# Metro_Mini_328_V2_-_STEMMA_QT.net
KiCad netlist of a schematic drawn in EAGLE
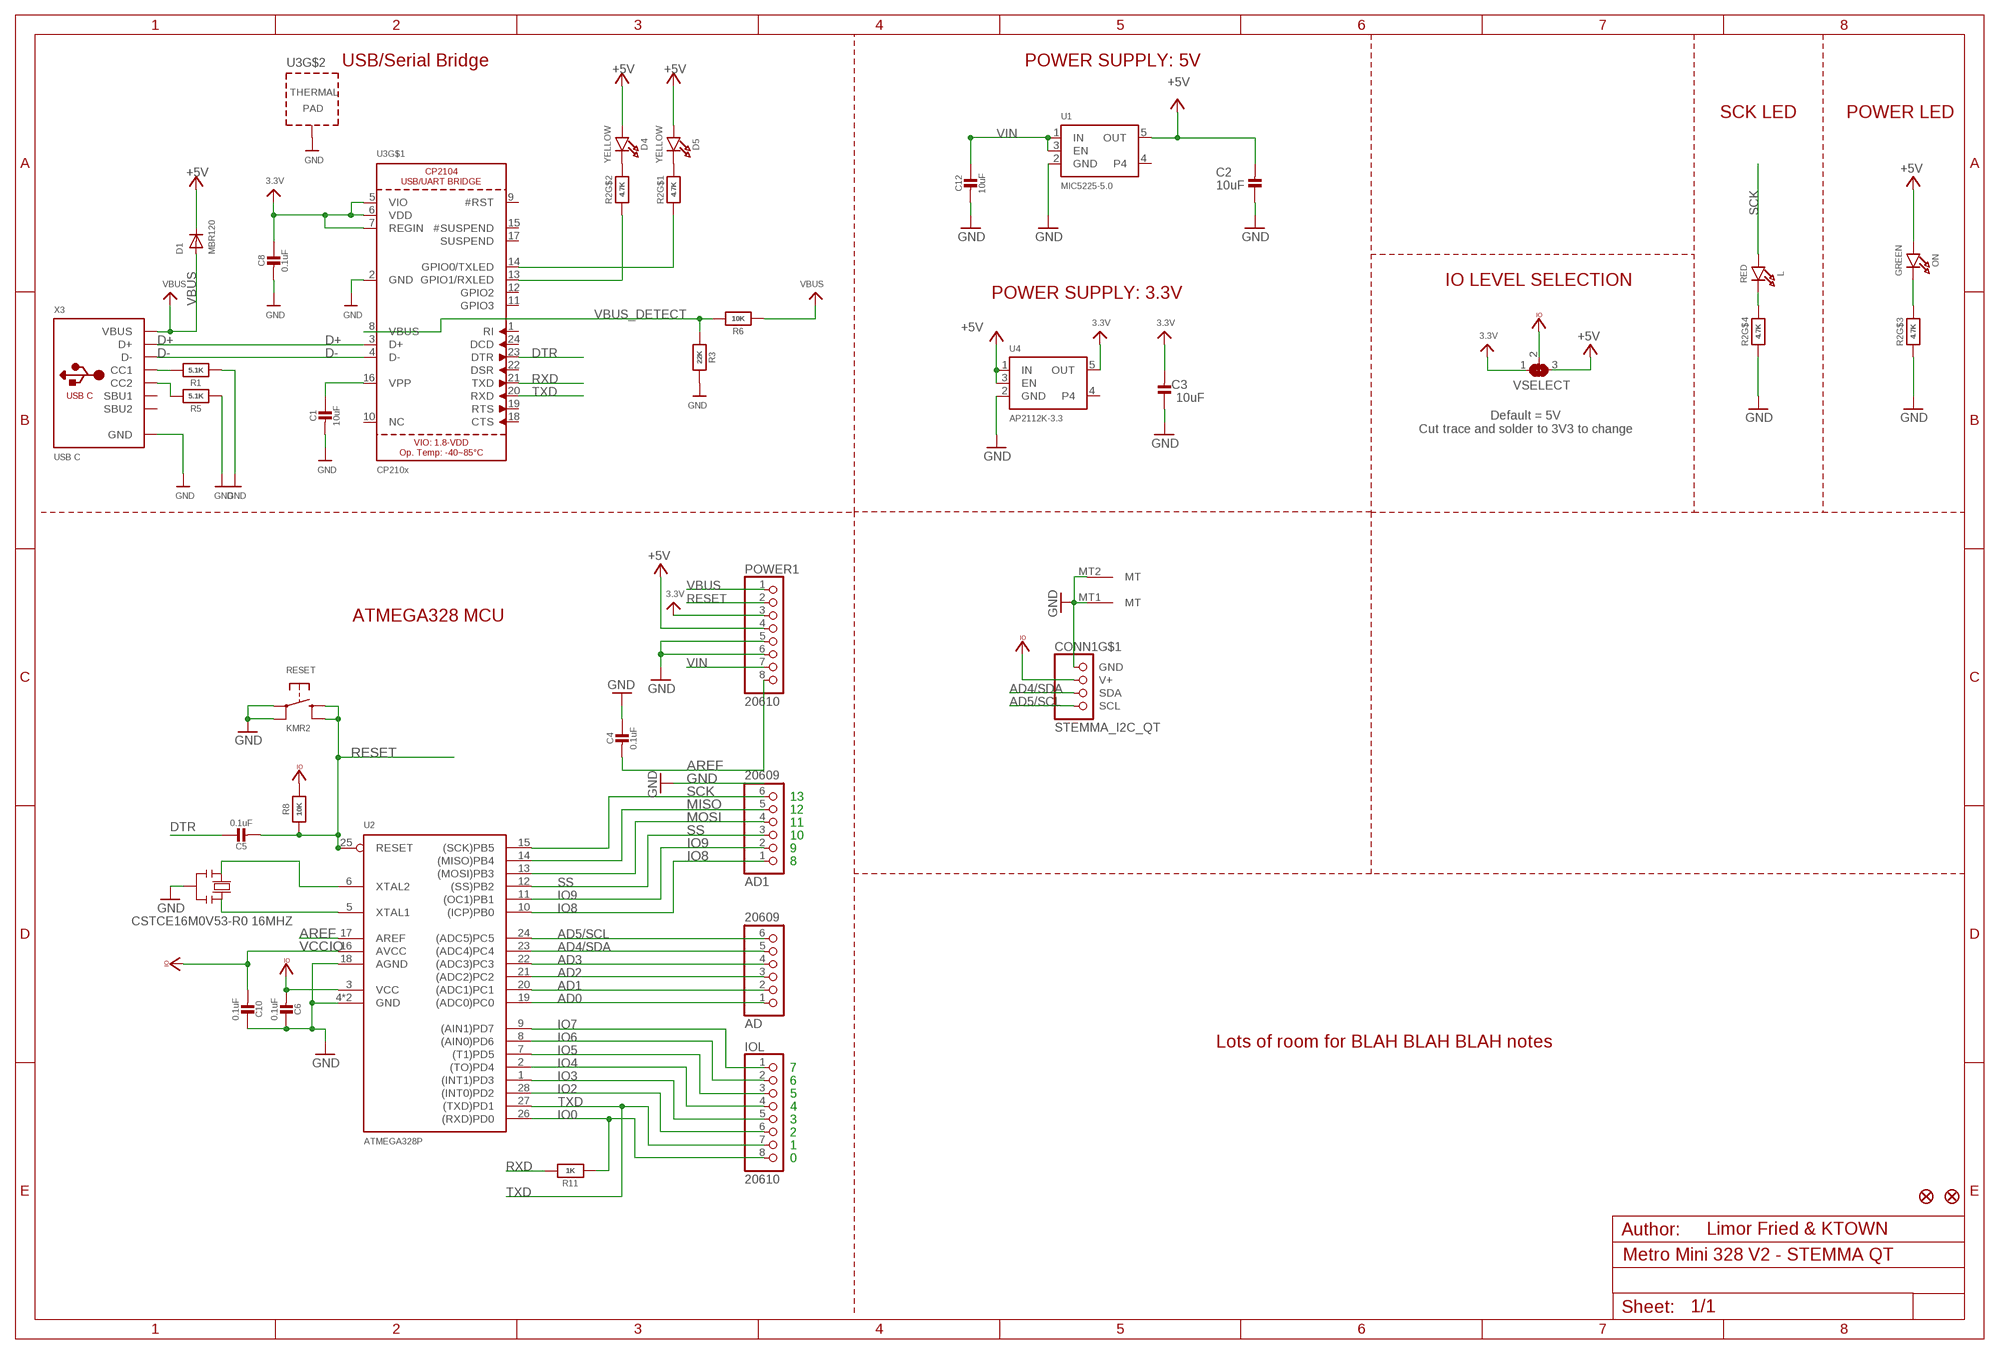
[diagram p0: schematic, sheet 1]

(export (version "E")
  (design (tool "Eeschema 10.0.6"))
  (components
    (comp (ref "AD")
      (value "20609")
      (footprint "eagle-import:1X06_ROUND")
      (libsource (lib "eagle-import") (part "HEADER-1X6ROUND"))
    )
    (comp (ref "AD1")
      (value "20609")
      (footprint "eagle-import:1X06_ROUND")
      (libsource (lib "eagle-import") (part "HEADER-1X6ROUND"))
    )
    (comp (ref "C1")
      (value "10uF")
      (footprint "eagle-import:0805-NO")
      (libsource (lib "eagle-import") (part "CAP_CERAMIC0805-NOOUTLINE"))
    )
    (comp (ref "C2")
      (value "10uF")
      (footprint "eagle-import:0805-NO")
      (libsource (lib "eagle-import") (part "CAP_CERAMIC0805-NOOUTLINE"))
    )
    (comp (ref "C3")
      (value "10uF")
      (footprint "eagle-import:0805-NO")
      (libsource (lib "eagle-import") (part "CAP_CERAMIC0805-NOOUTLINE"))
    )
    (comp (ref "C4")
      (value "0.1uF")
      (footprint "eagle-import:0603-NO")
      (libsource (lib "eagle-import") (part "CAP_CERAMIC0603_NO"))
    )
    (comp (ref "C5")
      (value "0.1uF")
      (footprint "eagle-import:0603-NO")
      (libsource (lib "eagle-import") (part "CAP_CERAMIC0603_NO"))
    )
    (comp (ref "C6")
      (value "0.1uF")
      (footprint "eagle-import:0603-NO")
      (libsource (lib "eagle-import") (part "CAP_CERAMIC0603_NO"))
    )
    (comp (ref "C8")
      (value "0.1uF")
      (footprint "eagle-import:0603-NO")
      (libsource (lib "eagle-import") (part "CAP_CERAMIC0603_NO"))
    )
    (comp (ref "C10")
      (value "0.1uF")
      (footprint "eagle-import:0603-NO")
      (libsource (lib "eagle-import") (part "CAP_CERAMIC0603_NO"))
    )
    (comp (ref "C12")
      (value "10uF")
      (footprint "eagle-import:0805-NO")
      (libsource (lib "eagle-import") (part "CAP_CERAMIC0805-NOOUTLINE"))
    )
    (comp (ref "CONN1")
      (value "STEMMA_I2C_QT")
      (footprint "eagle-import:JST_SH4")
      (libsource (lib "eagle-import") (part "STEMMA_I2C_QT"))
    )
    (comp (ref "D1")
      (value "MBR120")
      (footprint "eagle-import:SOD-123FL")
      (libsource (lib "eagle-import") (part "DIODE_MINISOD123"))
    )
    (comp (ref "D4")
      (value "YELLOW")
      (footprint "eagle-import:CHIPLED_0603_NOOUTLINE")
      (libsource (lib "eagle-import") (part "LED0603_NOOUTLINE"))
    )
    (comp (ref "D5")
      (value "YELLOW")
      (footprint "eagle-import:CHIPLED_0603_NOOUTLINE")
      (libsource (lib "eagle-import") (part "LED0603_NOOUTLINE"))
    )
    (comp (ref "FD1")
      (value "FIDUCIAL_1MM")
      (footprint "eagle-import:FIDUCIAL_1MM")
      (libsource (lib "eagle-import") (part "FIDUCIAL_1MM"))
    )
    (comp (ref "FD2")
      (value "FIDUCIAL_1MM")
      (footprint "eagle-import:FIDUCIAL_1MM")
      (libsource (lib "eagle-import") (part "FIDUCIAL_1MM"))
    )
    (comp (ref "IOL")
      (value "20610")
      (footprint "eagle-import:1X08_ROUND")
      (libsource (lib "eagle-import") (part "HEADER-1X8ROUND"))
    )
    (comp (ref "L")
      (value "RED")
      (footprint "eagle-import:CHIPLED_0603_NOOUTLINE")
      (libsource (lib "eagle-import") (part "LED0603_NOOUTLINE"))
    )
    (comp (ref "ON")
      (value "GREEN")
      (footprint "eagle-import:CHIPLED_0603_NOOUTLINE")
      (libsource (lib "eagle-import") (part "LED0603_NOOUTLINE"))
    )
    (comp (ref "POWER1")
      (value "20610")
      (footprint "eagle-import:1X08_ROUND_70")
      (libsource (lib "eagle-import") (part "HEADER-1X870MIL"))
    )
    (comp (ref "R1")
      (value "5.1K")
      (footprint "eagle-import:0603-NO")
      (libsource (lib "eagle-import") (part "RESISTOR_0603_NOOUT"))
    )
    (comp (ref "R2")
      (value "4.7K")
      (footprint "eagle-import:RESPACK_4X0603")
      (libsource (lib "eagle-import") (part "RESISTOR_4PACK"))
    )
    (comp (ref "R3")
      (value "22K")
      (footprint "eagle-import:0603-NO")
      (libsource (lib "eagle-import") (part "RESISTOR_0603_NOOUT"))
    )
    (comp (ref "R5")
      (value "5.1K")
      (footprint "eagle-import:0603-NO")
      (libsource (lib "eagle-import") (part "RESISTOR_0603_NOOUT"))
    )
    (comp (ref "R6")
      (value "10K")
      (footprint "eagle-import:0603-NO")
      (libsource (lib "eagle-import") (part "RESISTOR_0603_NOOUT"))
    )
    (comp (ref "R8")
      (value "10K")
      (footprint "eagle-import:0603-NO")
      (libsource (lib "eagle-import") (part "RESISTOR_0603_NOOUT"))
    )
    (comp (ref "R11")
      (value "1K")
      (footprint "eagle-import:0603-NO")
      (libsource (lib "eagle-import") (part "RESISTOR_0603_NOOUT"))
    )
    (comp (ref "RESET")
      (value "KMR2")
      (footprint "eagle-import:BTN_KMR2_4.6X2.8")
      (libsource (lib "eagle-import") (part "SWITCH_TACT_SMT4.6X2.8"))
    )
    (comp (ref "U1")
      (value "MIC5225-5.0")
      (footprint "eagle-import:SOT23-5")
      (libsource (lib "eagle-import") (part "VREG_SOT23-5"))
    )
    (comp (ref "U2")
      (value "ATMEGA328P")
      (footprint "eagle-import:QFN28_4MM_.45MM")
      (libsource (lib "eagle-import") (part "ATMEGA328P-MM"))
    )
    (comp (ref "U3")
      (value "CP210x")
      (footprint "eagle-import:QFN24_4MM_SMSC")
      (libsource (lib "eagle-import") (part "CP2104"))
    )
    (comp (ref "U4")
      (value "AP2112K-3.3")
      (footprint "eagle-import:SOT23-5")
      (libsource (lib "eagle-import") (part "VREG_SOT23-5"))
    )
    (comp (ref "VSELECT")
      (value "SOLDERJUMPER_2WAY")
      (footprint "eagle-import:SOLDERJUMPER_2WAY_OPEN_NOPASTE")
      (libsource (lib "eagle-import") (part "SOLDERJUMPER_2WAY"))
    )
    (comp (ref "X3")
      (value "USB C")
      (footprint "eagle-import:USB_C_CUSB31-CFM2AX-01-X")
      (libsource (lib "eagle-import") (part "USB_C"))
    )
    (comp (ref "Y2")
      (value "CSTCE16M0V53-R0 16MHZ")
      (footprint "eagle-import:RESONATOR")
      (libsource (lib "eagle-import") (part "RESONATORMU"))
    )
  )
  (nets
    (net (code "1") (name "+5V") (class "Default")
      (node (ref "C2") (pin "2") (pinfunction "2_2") (pintype "passive"))
      (node (ref "D1") (pin "C") (pinfunction "C_C") (pintype "passive"))
      (node (ref "D4") (pin "A") (pinfunction "A_A") (pintype "passive"))
      (node (ref "D5") (pin "A") (pinfunction "A_A") (pintype "passive"))
      (node (ref "ON") (pin "A") (pinfunction "A_A") (pintype "passive"))
      (node (ref "POWER1") (pin "4") (pinfunction "4_4") (pintype "passive"))
      (node (ref "U1") (pin "5") (pinfunction "OUT_5") (pintype "power_in"))
      (node (ref "U4") (pin "1") (pinfunction "IN_1") (pintype "power_in"))
      (node (ref "U4") (pin "3") (pinfunction "EN_3") (pintype "input"))
      (node (ref "VSELECT") (pin "3") (pinfunction "3_3") (pintype "passive"))
    )
    (net (code "2") (name "/AD0") (class "Default")
      (node (ref "AD") (pin "1") (pinfunction "1_1") (pintype "passive"))
      (node (ref "U2") (pin "19") (pinfunction "(ADC0)PC0_19") (pintype "bidirectional"))
    )
    (net (code "3") (name "/AD1") (class "Default")
      (node (ref "AD") (pin "2") (pinfunction "2_2") (pintype "passive"))
      (node (ref "U2") (pin "20") (pinfunction "(ADC1)PC1_20") (pintype "bidirectional"))
    )
    (net (code "4") (name "/AD2") (class "Default")
      (node (ref "AD") (pin "3") (pinfunction "3_3") (pintype "passive"))
      (node (ref "U2") (pin "21") (pinfunction "(ADC2)PC2_21") (pintype "bidirectional"))
    )
    (net (code "5") (name "/AD3") (class "Default")
      (node (ref "AD") (pin "4") (pinfunction "4_4") (pintype "passive"))
      (node (ref "U2") (pin "22") (pinfunction "(ADC3)PC3_22") (pintype "bidirectional"))
    )
    (net (code "6") (name "/AD4{slash}SDA") (class "Default")
      (node (ref "AD") (pin "5") (pinfunction "5_5") (pintype "passive"))
      (node (ref "CONN1") (pin "3") (pinfunction "SDA_3") (pintype "passive"))
      (node (ref "U2") (pin "23") (pinfunction "(ADC4)PC4_23") (pintype "bidirectional"))
    )
    (net (code "7") (name "/AD5{slash}SCL") (class "Default")
      (node (ref "AD") (pin "6") (pinfunction "6_6") (pintype "passive"))
      (node (ref "CONN1") (pin "4") (pinfunction "SCL_4") (pintype "passive"))
      (node (ref "U2") (pin "24") (pinfunction "(ADC5)PC5_24") (pintype "bidirectional"))
    )
    (net (code "8") (name "/AREF") (class "Default")
      (node (ref "C4") (pin "2") (pinfunction "2_2") (pintype "passive"))
      (node (ref "POWER1") (pin "8") (pinfunction "8_8") (pintype "passive"))
      (node (ref "U2") (pin "17") (pinfunction "AREF_17") (pintype "power_in"))
    )
    (net (code "9") (name "/D+") (class "Default")
      (node (ref "U3") (pin "3") (pinfunction "D+_3") (pintype "bidirectional"))
      (node (ref "X3") (pin "A6") (pinfunction "D+_A6") (pintype "bidirectional"))
      (node (ref "X3") (pin "B6") (pinfunction "D+_B6") (pintype "bidirectional"))
    )
    (net (code "10") (name "/D-") (class "Default")
      (node (ref "U3") (pin "4") (pinfunction "D-_4") (pintype "bidirectional"))
      (node (ref "X3") (pin "A7") (pinfunction "D-_A7") (pintype "bidirectional"))
      (node (ref "X3") (pin "B7") (pinfunction "D-_B7") (pintype "bidirectional"))
    )
    (net (code "11") (name "/DTR") (class "Default")
      (node (ref "C5") (pin "1") (pinfunction "1_1") (pintype "passive"))
      (node (ref "U3") (pin "23") (pinfunction "DTR_23") (pintype "output"))
    )
    (net (code "12") (name "/IO0") (class "Default")
      (node (ref "IOL") (pin "8") (pinfunction "8_8") (pintype "passive"))
      (node (ref "R11") (pin "1") (pinfunction "1_1") (pintype "passive"))
      (node (ref "U2") (pin "26") (pinfunction "(RXD)PD0_26") (pintype "bidirectional"))
    )
    (net (code "13") (name "/IO2") (class "Default")
      (node (ref "IOL") (pin "6") (pinfunction "6_6") (pintype "passive"))
      (node (ref "U2") (pin "28") (pinfunction "(INT0)PD2_28") (pintype "bidirectional"))
    )
    (net (code "14") (name "/IO3") (class "Default")
      (node (ref "IOL") (pin "5") (pinfunction "5_5") (pintype "passive"))
      (node (ref "U2") (pin "1") (pinfunction "(INT1)PD3_1") (pintype "bidirectional"))
    )
    (net (code "15") (name "/IO4") (class "Default")
      (node (ref "IOL") (pin "4") (pinfunction "4_4") (pintype "passive"))
      (node (ref "U2") (pin "2") (pinfunction "(TO)PD4_2") (pintype "bidirectional"))
    )
    (net (code "16") (name "/IO5") (class "Default")
      (node (ref "IOL") (pin "3") (pinfunction "3_3") (pintype "passive"))
      (node (ref "U2") (pin "7") (pinfunction "(T1)PD5_7") (pintype "bidirectional"))
    )
    (net (code "17") (name "/IO6") (class "Default")
      (node (ref "IOL") (pin "2") (pinfunction "2_2") (pintype "passive"))
      (node (ref "U2") (pin "8") (pinfunction "(AIN0)PD6_8") (pintype "bidirectional"))
    )
    (net (code "18") (name "/IO7") (class "Default")
      (node (ref "IOL") (pin "1") (pinfunction "1_1") (pintype "passive"))
      (node (ref "U2") (pin "9") (pinfunction "(AIN1)PD7_9") (pintype "bidirectional"))
    )
    (net (code "19") (name "/IO8") (class "Default")
      (node (ref "AD1") (pin "1") (pinfunction "1_1") (pintype "passive"))
      (node (ref "U2") (pin "10") (pinfunction "(ICP)PB0_10") (pintype "bidirectional"))
    )
    (net (code "20") (name "/IO9") (class "Default")
      (node (ref "AD1") (pin "2") (pinfunction "2_2") (pintype "passive"))
      (node (ref "U2") (pin "11") (pinfunction "(OC1)PB1_11") (pintype "bidirectional"))
    )
    (net (code "21") (name "/MISO") (class "Default")
      (node (ref "AD1") (pin "5") (pinfunction "5_5") (pintype "passive"))
      (node (ref "U2") (pin "14") (pinfunction "(MISO)PB4_14") (pintype "bidirectional"))
    )
    (net (code "22") (name "/MOSI") (class "Default")
      (node (ref "AD1") (pin "4") (pinfunction "4_4") (pintype "passive"))
      (node (ref "U2") (pin "13") (pinfunction "(MOSI)PB3_13") (pintype "bidirectional"))
    )
    (net (code "23") (name "/RESET") (class "Default")
      (node (ref "C5") (pin "2") (pinfunction "2_2") (pintype "passive"))
      (node (ref "POWER1") (pin "2") (pinfunction "2_2") (pintype "passive"))
      (node (ref "R8") (pin "1") (pinfunction "1_1") (pintype "passive"))
      (node (ref "RESET") (pin "B") (pinfunction "S_B") (pintype "passive"))
      (node (ref "RESET") (pin "B'") (pinfunction "S1_B'") (pintype "passive"))
      (node (ref "U2") (pin "25") (pinfunction "RESET_25") (pintype "bidirectional"))
    )
    (net (code "24") (name "/RXD") (class "Default")
      (node (ref "R11") (pin "2") (pinfunction "2_2") (pintype "passive"))
      (node (ref "U3") (pin "21") (pinfunction "TXD_21") (pintype "output"))
    )
    (net (code "25") (name "/SCK") (class "Default")
      (node (ref "AD1") (pin "6") (pinfunction "6_6") (pintype "passive"))
      (node (ref "L") (pin "A") (pinfunction "A_A") (pintype "passive"))
      (node (ref "U2") (pin "15") (pinfunction "(SCK)PB5_15") (pintype "bidirectional"))
    )
    (net (code "26") (name "/SS") (class "Default")
      (node (ref "AD1") (pin "3") (pinfunction "3_3") (pintype "passive"))
      (node (ref "U2") (pin "12") (pinfunction "(SS)PB2_12") (pintype "bidirectional"))
    )
    (net (code "27") (name "/TXD") (class "Default")
      (node (ref "IOL") (pin "7") (pinfunction "7_7") (pintype "passive"))
      (node (ref "U2") (pin "27") (pinfunction "(TXD)PD1_27") (pintype "bidirectional"))
      (node (ref "U3") (pin "20") (pinfunction "RXD_20") (pintype "input"))
    )
    (net (code "28") (name "/VBUS_DETECT") (class "Default")
      (node (ref "R3") (pin "2") (pinfunction "2_2") (pintype "passive"))
      (node (ref "R6") (pin "1") (pinfunction "1_1") (pintype "passive"))
      (node (ref "U3") (pin "8") (pinfunction "VBUS_8") (pintype "power_in"))
    )
    (net (code "29") (name "/VIN") (class "Default")
      (node (ref "C12") (pin "1") (pinfunction "1_1") (pintype "passive"))
      (node (ref "POWER1") (pin "7") (pinfunction "7_7") (pintype "passive"))
      (node (ref "U1") (pin "1") (pinfunction "IN_1") (pintype "power_in"))
      (node (ref "U1") (pin "3") (pinfunction "EN_3") (pintype "input"))
    )
    (net (code "30") (name "3.3V") (class "Default")
      (node (ref "C3") (pin "2") (pinfunction "2_2") (pintype "passive"))
      (node (ref "C8") (pin "1") (pinfunction "1_1") (pintype "passive"))
      (node (ref "POWER1") (pin "3") (pinfunction "3_3") (pintype "passive"))
      (node (ref "U3") (pin "5") (pinfunction "VIO_5") (pintype "power_in"))
      (node (ref "U3") (pin "6") (pinfunction "VDD_6") (pintype "power_in"))
      (node (ref "U3") (pin "7") (pinfunction "REGIN_7") (pintype "power_in"))
      (node (ref "U4") (pin "5") (pinfunction "OUT_5") (pintype "power_in"))
      (node (ref "VSELECT") (pin "1") (pinfunction "1_1") (pintype "passive"))
    )
    (net (code "31") (name "GND") (class "Default")
      (node (ref "C1") (pin "2") (pinfunction "2_2") (pintype "passive"))
      (node (ref "C10") (pin "1") (pinfunction "1_1") (pintype "passive"))
      (node (ref "C12") (pin "2") (pinfunction "2_2") (pintype "passive"))
      (node (ref "C2") (pin "1") (pinfunction "1_1") (pintype "passive"))
      (node (ref "C3") (pin "1") (pinfunction "1_1") (pintype "passive"))
      (node (ref "C4") (pin "1") (pinfunction "1_1") (pintype "passive"))
      (node (ref "C6") (pin "1") (pinfunction "1_1") (pintype "passive"))
      (node (ref "C8") (pin "2") (pinfunction "2_2") (pintype "passive"))
      (node (ref "CONN1") (pin "1") (pinfunction "GND_1") (pintype "passive"))
      (node (ref "CONN1") (pin "MT1") (pinfunction "MT_MT1") (pintype "bidirectional"))
      (node (ref "CONN1") (pin "MT2") (pinfunction "MT_MT2") (pintype "bidirectional"))
      (node (ref "POWER1") (pin "5") (pinfunction "5_5") (pintype "passive"))
      (node (ref "POWER1") (pin "6") (pinfunction "6_6") (pintype "passive"))
      (node (ref "R1") (pin "1") (pinfunction "1_1") (pintype "passive"))
      (node (ref "R2") (pin "3") (pinfunction "1_3") (pintype "passive"))
      (node (ref "R2") (pin "4") (pinfunction "1_4") (pintype "passive"))
      (node (ref "R3") (pin "1") (pinfunction "1_1") (pintype "passive"))
      (node (ref "R5") (pin "1") (pinfunction "1_1") (pintype "passive"))
      (node (ref "RESET") (pin "A") (pinfunction "P_A") (pintype "passive"))
      (node (ref "RESET") (pin "A'") (pinfunction "P1_A'") (pintype "passive"))
      (node (ref "U1") (pin "2") (pinfunction "GND_2") (pintype "power_in"))
      (node (ref "U2") (pin "18") (pinfunction "AGND_18") (pintype "power_in"))
      (node (ref "U2") (pin "29") (pinfunction "GND_29") (pintype "power_in"))
      (node (ref "U2") (pin "4") (pinfunction "GND_4") (pintype "power_in"))
      (node (ref "U3") (pin "2") (pinfunction "GND_2") (pintype "power_in"))
      (node (ref "U3") (pin "THERM") (pinfunction "TP_THERM") (pintype "power_in"))
      (node (ref "U4") (pin "2") (pinfunction "GND_2") (pintype "power_in"))
      (node (ref "X3") (pin "A1B12") (pinfunction "GND_A1B12") (pintype "power_in"))
      (node (ref "X3") (pin "B1A12") (pinfunction "GND_B1A12") (pintype "power_in"))
      (node (ref "Y2") (pin "2") (pinfunction "2_2") (pintype "passive"))
    )
    (net (code "32") (name "Net-(R2A-2)") (class "Default")
      (node (ref "D5") (pin "C") (pinfunction "C_C") (pintype "passive"))
      (node (ref "R2") (pin "8") (pinfunction "2_8") (pintype "passive"))
    )
    (net (code "33") (name "Net-(R2B-1)") (class "Default")
      (node (ref "R2") (pin "2") (pinfunction "1_2") (pintype "passive"))
      (node (ref "U3") (pin "13") (pinfunction "GPIO1/RXLED_13") (pintype "bidirectional"))
    )
    (net (code "34") (name "Net-(R2B-2)") (class "Default")
      (node (ref "D4") (pin "C") (pinfunction "C_C") (pintype "passive"))
      (node (ref "R2") (pin "7") (pinfunction "2_7") (pintype "passive"))
    )
    (net (code "35") (name "Net-(R2C-2)") (class "Default")
      (node (ref "ON") (pin "C") (pinfunction "C_C") (pintype "passive"))
      (node (ref "R2") (pin "6") (pinfunction "2_6") (pintype "passive"))
    )
    (net (code "36") (name "Net-(R2D-2)") (class "Default")
      (node (ref "L") (pin "C") (pinfunction "C_C") (pintype "passive"))
      (node (ref "R2") (pin "5") (pinfunction "2_5") (pintype "passive"))
    )
    (net (code "37") (name "Net-(U2-XTAL1)") (class "Default")
      (node (ref "U2") (pin "5") (pinfunction "XTAL1_5") (pintype "bidirectional"))
      (node (ref "Y2") (pin "3") (pinfunction "3_3") (pintype "passive"))
    )
    (net (code "38") (name "Net-(U2-XTAL2)") (class "Default")
      (node (ref "U2") (pin "6") (pinfunction "XTAL2_6") (pintype "bidirectional"))
      (node (ref "Y2") (pin "1") (pinfunction "1_1") (pintype "passive"))
    )
    (net (code "39") (name "Net-(U3A-GPIO0{slash}TXLED)") (class "Default")
      (node (ref "R2") (pin "1") (pinfunction "1_1") (pintype "passive"))
      (node (ref "U3") (pin "14") (pinfunction "GPIO0/TXLED_14") (pintype "bidirectional"))
    )
    (net (code "40") (name "Net-(U3A-VPP)") (class "Default")
      (node (ref "C1") (pin "1") (pinfunction "1_1") (pintype "passive"))
      (node (ref "U3") (pin "16") (pinfunction "VPP_16") (pintype "bidirectional"))
    )
    (net (code "41") (name "Net-(X3-CC1)") (class "Default")
      (node (ref "R1") (pin "2") (pinfunction "2_2") (pintype "passive"))
      (node (ref "X3") (pin "A5") (pinfunction "CC1_A5") (pintype "bidirectional"))
    )
    (net (code "42") (name "Net-(X3-CC2)") (class "Default")
      (node (ref "R5") (pin "2") (pinfunction "2_2") (pintype "passive"))
      (node (ref "X3") (pin "B5") (pinfunction "CC2_B5") (pintype "bidirectional"))
    )
    (net (code "43") (name "VBUS") (class "Default")
      (node (ref "D1") (pin "A") (pinfunction "A_A") (pintype "passive"))
      (node (ref "POWER1") (pin "1") (pinfunction "1_1") (pintype "passive"))
      (node (ref "R6") (pin "2") (pinfunction "2_2") (pintype "passive"))
      (node (ref "X3") (pin "A4B9") (pinfunction "VBUS_A4B9") (pintype "power_in"))
      (node (ref "X3") (pin "B4A9") (pinfunction "VBUS_B4A9") (pintype "power_in"))
    )
    (net (code "44") (name "VCCIO") (class "Default")
      (node (ref "C10") (pin "2") (pinfunction "2_2") (pintype "passive"))
      (node (ref "C6") (pin "2") (pinfunction "2_2") (pintype "passive"))
      (node (ref "CONN1") (pin "2") (pinfunction "V+_2") (pintype "passive"))
      (node (ref "R8") (pin "2") (pinfunction "2_2") (pintype "passive"))
      (node (ref "U2") (pin "16") (pinfunction "AVCC_16") (pintype "power_in"))
      (node (ref "U2") (pin "3") (pinfunction "VCC_3") (pintype "power_in"))
      (node (ref "VSELECT") (pin "2") (pinfunction "2_2") (pintype "passive"))
    )
    (net (code "45") (name "unconnected-(U1-P4-Pad4)") (class "Default")
      (node (ref "U1") (pin "4") (pinfunction "P4_4") (pintype "bidirectional"))
    )
    (net (code "46") (name "unconnected-(U3A-#RST-Pad9)") (class "Default")
      (node (ref "U3") (pin "9") (pinfunction "#RST_9") (pintype "bidirectional"))
    )
    (net (code "47") (name "unconnected-(U3A-#SUSPEND-Pad15)") (class "Default")
      (node (ref "U3") (pin "15") (pinfunction "#SUSPEND_15") (pintype "output"))
    )
    (net (code "48") (name "unconnected-(U3A-CTS-Pad18)") (class "Default")
      (node (ref "U3") (pin "18") (pinfunction "CTS_18") (pintype "input"))
    )
    (net (code "49") (name "unconnected-(U3A-DCD-Pad24)") (class "Default")
      (node (ref "U3") (pin "24") (pinfunction "DCD_24") (pintype "input"))
    )
    (net (code "50") (name "unconnected-(U3A-DSR-Pad22)") (class "Default")
      (node (ref "U3") (pin "22") (pinfunction "DSR_22") (pintype "input"))
    )
    (net (code "51") (name "unconnected-(U3A-GPIO2-Pad12)") (class "Default")
      (node (ref "U3") (pin "12") (pinfunction "GPIO2_12") (pintype "bidirectional"))
    )
    (net (code "52") (name "unconnected-(U3A-GPIO3-Pad11)") (class "Default")
      (node (ref "U3") (pin "11") (pinfunction "GPIO3_11") (pintype "bidirectional"))
    )
    (net (code "53") (name "unconnected-(U3A-NC-Pad10)") (class "Default")
      (node (ref "U3") (pin "10") (pinfunction "NC_10") (pintype "no_connect"))
    )
    (net (code "54") (name "unconnected-(U3A-RI-Pad1)") (class "Default")
      (node (ref "U3") (pin "1") (pinfunction "RI_1") (pintype "input"))
    )
    (net (code "55") (name "unconnected-(U3A-RTS-Pad19)") (class "Default")
      (node (ref "U3") (pin "19") (pinfunction "RTS_19") (pintype "output"))
    )
    (net (code "56") (name "unconnected-(U3A-SUSPEND-Pad17)") (class "Default")
      (node (ref "U3") (pin "17") (pinfunction "SUSPEND_17") (pintype "output"))
    )
    (net (code "57") (name "unconnected-(U4-P4-Pad4)") (class "Default")
      (node (ref "U4") (pin "4") (pinfunction "P4_4") (pintype "bidirectional"))
    )
    (net (code "58") (name "unconnected-(X3-SBU1-PadA8)") (class "Default")
      (node (ref "X3") (pin "A8") (pinfunction "SBU1_A8") (pintype "bidirectional"))
    )
    (net (code "59") (name "unconnected-(X3-SBU2-PadB8)") (class "Default")
      (node (ref "X3") (pin "B8") (pinfunction "SBU2_B8") (pintype "bidirectional"))
    )
  )
)
